# MBC5_1-4.net
KiCad netlist of a schematic drawn in EAGLE
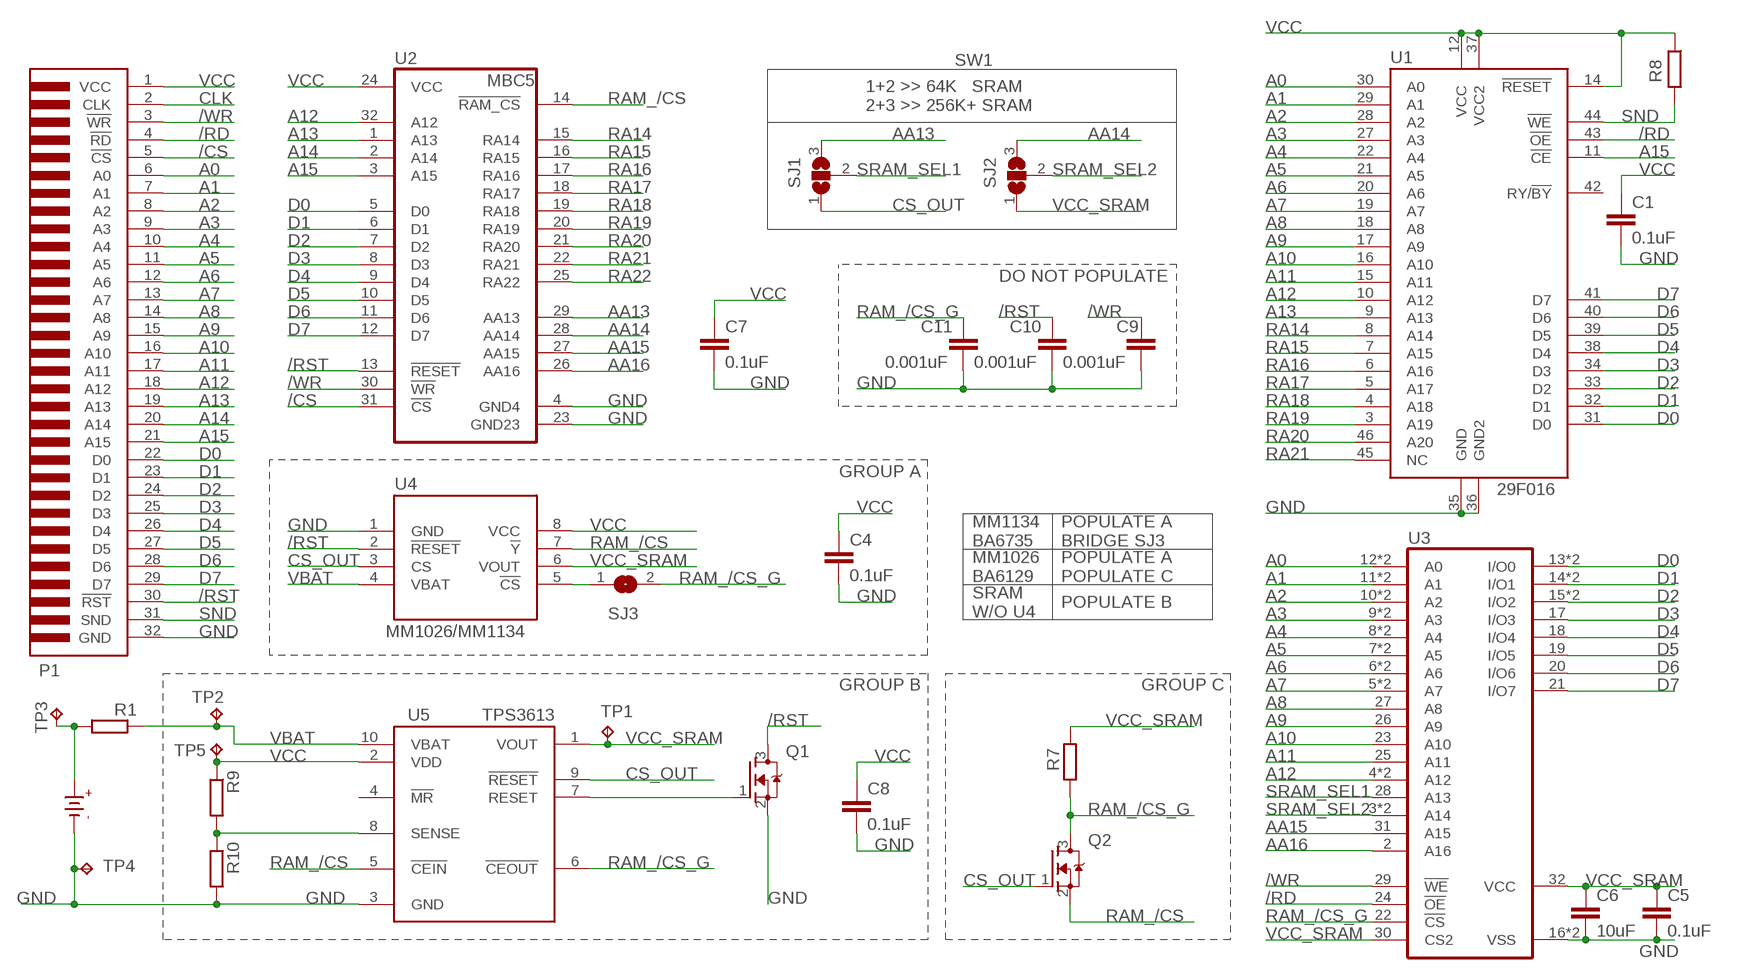
[diagram p0: schematic, sheet 1]

(export (version "E")
  (design (tool "Eeschema 10.0.6"))
  (components
    (comp (ref "B1")
      (value "CR2025")
      (footprint "eagle-import:CR2025")
      (libsource (lib "eagle-import") (part "CR2025"))
    )
    (comp (ref "C1")
      (value "0.1uF")
      (footprint "eagle-import:C0603")
      (libsource (lib "eagle-import") (part "C-EUC0603"))
    )
    (comp (ref "C4")
      (value "0.1uF")
      (footprint "eagle-import:C0603")
      (libsource (lib "eagle-import") (part "C-EUC0603"))
    )
    (comp (ref "C5")
      (value "0.1uF")
      (footprint "eagle-import:C0603")
      (libsource (lib "eagle-import") (part "C-EUC0603"))
    )
    (comp (ref "C6")
      (value "10uF")
      (footprint "eagle-import:C0603")
      (libsource (lib "eagle-import") (part "C-EUC0603"))
    )
    (comp (ref "C7")
      (value "0.1uF")
      (footprint "eagle-import:C0603")
      (libsource (lib "eagle-import") (part "C-EUC0603"))
    )
    (comp (ref "C8")
      (value "0.1uF")
      (footprint "eagle-import:C0603")
      (libsource (lib "eagle-import") (part "C-EUC0603"))
    )
    (comp (ref "C9")
      (value "0.001uF")
      (footprint "eagle-import:C0603")
      (libsource (lib "eagle-import") (part "C-EUC0603"))
    )
    (comp (ref "C10")
      (value "0.001uF")
      (footprint "eagle-import:C0603")
      (libsource (lib "eagle-import") (part "C-EUC0603"))
    )
    (comp (ref "C11")
      (value "0.001uF")
      (footprint "eagle-import:C0603")
      (libsource (lib "eagle-import") (part "C-EUC0603"))
    )
    (comp (ref "P1")
      (value "GBC_CARTTAB")
      (footprint "eagle-import:GBC_CART_TABBED")
      (libsource (lib "eagle-import") (part "GBC_CARTTAB"))
    )
    (comp (ref "Q1")
      (value "2N7002")
      (footprint "eagle-import:SOT23")
      (libsource (lib "eagle-import") (part "MOSFET-NREFLOW"))
    )
    (comp (ref "Q2")
      (value "2N7002")
      (footprint "eagle-import:SOT23")
      (libsource (lib "eagle-import") (part "MOSFET-NREFLOW"))
    )
    (comp (ref "R1")
      (value "RR0603")
      (footprint "eagle-import:R0603")
      (libsource (lib "eagle-import") (part "RR0603"))
    )
    (comp (ref "R7")
      (value "RR0603")
      (footprint "eagle-import:R0603")
      (libsource (lib "eagle-import") (part "RR0603"))
    )
    (comp (ref "R8")
      (value "RR0603")
      (footprint "eagle-import:R0603")
      (libsource (lib "eagle-import") (part "RR0603"))
    )
    (comp (ref "R9")
      (value "RR0603")
      (footprint "eagle-import:R0603")
      (libsource (lib "eagle-import") (part "RR0603"))
    )
    (comp (ref "R10")
      (value "RR0603")
      (footprint "eagle-import:R0603")
      (libsource (lib "eagle-import") (part "RR0603"))
    )
    (comp (ref "SJ1")
      (value "SJ2W")
      (footprint "eagle-import:SJ_2")
      (libsource (lib "eagle-import") (part "SJ2W"))
    )
    (comp (ref "SJ2")
      (value "SJ2W")
      (footprint "eagle-import:SJ_2")
      (libsource (lib "eagle-import") (part "SJ2W"))
    )
    (comp (ref "SJ3") (value "SJ") (footprint "eagle-import:SJ") (libsource (lib "eagle-import") (part "SJ")))
    (comp (ref "TP1")
      (value "TPB1,27")
      (footprint "eagle-import:B1,27")
      (libsource (lib "eagle-import") (part "TPB1,27"))
    )
    (comp (ref "TP2")
      (value "TPB1,27")
      (footprint "eagle-import:B1,27")
      (libsource (lib "eagle-import") (part "TPB1,27"))
    )
    (comp (ref "TP3")
      (value "TPB1,27")
      (footprint "eagle-import:B1,27")
      (libsource (lib "eagle-import") (part "TPB1,27"))
    )
    (comp (ref "TP4")
      (value "TPB1,27")
      (footprint "eagle-import:B1,27")
      (libsource (lib "eagle-import") (part "TPB1,27"))
    )
    (comp (ref "TP5")
      (value "TPB1,27")
      (footprint "eagle-import:B1,27")
      (libsource (lib "eagle-import") (part "TPB1,27"))
    )
    (comp (ref "U1")
      (value "29F016")
      (footprint "eagle-import:TSOP-48")
      (libsource (lib "eagle-import") (part "29F016"))
    )
    (comp (ref "U2")
      (value "MBC5")
      (footprint "eagle-import:QFP-32")
      (libsource (lib "eagle-import") (part "MBC5"))
    )
    (comp (ref "U3")
      (value "1008L")
      (footprint "eagle-import:SO32L_L")
      (libsource (lib "eagle-import") (part "1008L"))
    )
    (comp (ref "U4")
      (value "MM1134")
      (footprint "eagle-import:SOIC-8")
      (libsource (lib "eagle-import") (part "MM1134"))
    )
    (comp (ref "U5")
      (value "TPS3613")
      (footprint "eagle-import:MSOP-10")
      (libsource (lib "eagle-import") (part "TPS3613"))
    )
  )
  (nets
    (net (code "1") (name "/A0") (class "Default")
      (node (ref "P1") (pin "6") (pinfunction "A0_6") (pintype "output"))
      (node (ref "U1") (pin "30") (pinfunction "A0_30") (pintype "input"))
      (node (ref "U3") (pin "12") (pinfunction "A0_12") (pintype "input"))
      (node (ref "U3") (pin "L12") (pinfunction "A0_L12") (pintype "input"))
    )
    (net (code "2") (name "/A1") (class "Default")
      (node (ref "P1") (pin "7") (pinfunction "A1_7") (pintype "output"))
      (node (ref "U1") (pin "29") (pinfunction "A1_29") (pintype "input"))
      (node (ref "U3") (pin "11") (pinfunction "A1_11") (pintype "input"))
      (node (ref "U3") (pin "L11") (pinfunction "A1_L11") (pintype "input"))
    )
    (net (code "3") (name "/A2") (class "Default")
      (node (ref "P1") (pin "8") (pinfunction "A2_8") (pintype "output"))
      (node (ref "U1") (pin "28") (pinfunction "A2_28") (pintype "input"))
      (node (ref "U3") (pin "10") (pinfunction "A2_10") (pintype "input"))
      (node (ref "U3") (pin "L10") (pinfunction "A2_L10") (pintype "input"))
    )
    (net (code "4") (name "/A3") (class "Default")
      (node (ref "P1") (pin "9") (pinfunction "A3_9") (pintype "output"))
      (node (ref "U1") (pin "27") (pinfunction "A3_27") (pintype "input"))
      (node (ref "U3") (pin "9") (pinfunction "A3_9") (pintype "input"))
      (node (ref "U3") (pin "L9") (pinfunction "A3_L9") (pintype "input"))
    )
    (net (code "5") (name "/A4") (class "Default")
      (node (ref "P1") (pin "10") (pinfunction "A4_10") (pintype "output"))
      (node (ref "U1") (pin "22") (pinfunction "A4_22") (pintype "input"))
      (node (ref "U3") (pin "8") (pinfunction "A4_8") (pintype "input"))
      (node (ref "U3") (pin "L8") (pinfunction "A4_L8") (pintype "input"))
    )
    (net (code "6") (name "/A5") (class "Default")
      (node (ref "P1") (pin "11") (pinfunction "A5_11") (pintype "output"))
      (node (ref "U1") (pin "21") (pinfunction "A5_21") (pintype "input"))
      (node (ref "U3") (pin "7") (pinfunction "A5_7") (pintype "input"))
      (node (ref "U3") (pin "L7") (pinfunction "A5_L7") (pintype "input"))
    )
    (net (code "7") (name "/A6") (class "Default")
      (node (ref "P1") (pin "12") (pinfunction "A6_12") (pintype "output"))
      (node (ref "U1") (pin "20") (pinfunction "A6_20") (pintype "input"))
      (node (ref "U3") (pin "6") (pinfunction "A6_6") (pintype "input"))
      (node (ref "U3") (pin "L6") (pinfunction "A6_L6") (pintype "input"))
    )
    (net (code "8") (name "/A7") (class "Default")
      (node (ref "P1") (pin "13") (pinfunction "A7_13") (pintype "output"))
      (node (ref "U1") (pin "19") (pinfunction "A7_19") (pintype "input"))
      (node (ref "U3") (pin "5") (pinfunction "A7_5") (pintype "input"))
      (node (ref "U3") (pin "L5") (pinfunction "A7_L5") (pintype "input"))
    )
    (net (code "9") (name "/A8") (class "Default")
      (node (ref "P1") (pin "14") (pinfunction "A8_14") (pintype "output"))
      (node (ref "U1") (pin "18") (pinfunction "A8_18") (pintype "input"))
      (node (ref "U3") (pin "27") (pinfunction "A8_27") (pintype "input"))
    )
    (net (code "10") (name "/A9") (class "Default")
      (node (ref "P1") (pin "15") (pinfunction "A9_15") (pintype "output"))
      (node (ref "U1") (pin "17") (pinfunction "A9_17") (pintype "input"))
      (node (ref "U3") (pin "26") (pinfunction "A9_26") (pintype "input"))
    )
    (net (code "11") (name "/A10") (class "Default")
      (node (ref "P1") (pin "16") (pinfunction "A10_16") (pintype "output"))
      (node (ref "U1") (pin "16") (pinfunction "A10_16") (pintype "input"))
      (node (ref "U3") (pin "23") (pinfunction "A10_23") (pintype "input"))
    )
    (net (code "12") (name "/A11") (class "Default")
      (node (ref "P1") (pin "17") (pinfunction "A11_17") (pintype "output"))
      (node (ref "U1") (pin "15") (pinfunction "A11_15") (pintype "input"))
      (node (ref "U3") (pin "25") (pinfunction "A11_25") (pintype "input"))
    )
    (net (code "13") (name "/A12") (class "Default")
      (node (ref "P1") (pin "18") (pinfunction "A12_18") (pintype "output"))
      (node (ref "U1") (pin "10") (pinfunction "A12_10") (pintype "input"))
      (node (ref "U2") (pin "32") (pinfunction "A12_32") (pintype "input"))
      (node (ref "U3") (pin "4") (pinfunction "A12_4") (pintype "input"))
      (node (ref "U3") (pin "L4") (pinfunction "A12_L4") (pintype "input"))
    )
    (net (code "14") (name "/A13") (class "Default")
      (node (ref "P1") (pin "19") (pinfunction "A13_19") (pintype "output"))
      (node (ref "U1") (pin "9") (pinfunction "A13_9") (pintype "input"))
      (node (ref "U2") (pin "1") (pinfunction "A13_1") (pintype "input"))
    )
    (net (code "15") (name "/A14") (class "Default")
      (node (ref "P1") (pin "20") (pinfunction "A14_20") (pintype "output"))
      (node (ref "U2") (pin "2") (pinfunction "A14_2") (pintype "input"))
    )
    (net (code "16") (name "/A15") (class "Default")
      (node (ref "P1") (pin "21") (pinfunction "A15_21") (pintype "output"))
      (node (ref "U1") (pin "11") (pinfunction "~{CE}_11") (pintype "input"))
      (node (ref "U2") (pin "3") (pinfunction "A15_3") (pintype "input"))
    )
    (net (code "17") (name "/AA13") (class "Default")
      (node (ref "SJ1") (pin "3") (pinfunction "3_3") (pintype "passive"))
      (node (ref "U2") (pin "29") (pinfunction "AA13_29") (pintype "output"))
    )
    (net (code "18") (name "/AA14") (class "Default")
      (node (ref "SJ2") (pin "3") (pinfunction "3_3") (pintype "passive"))
      (node (ref "U2") (pin "28") (pinfunction "AA14_28") (pintype "output"))
    )
    (net (code "19") (name "/AA15") (class "Default")
      (node (ref "U2") (pin "27") (pinfunction "AA15_27") (pintype "output"))
      (node (ref "U3") (pin "31") (pinfunction "A15_31") (pintype "input"))
    )
    (net (code "20") (name "/AA16") (class "Default")
      (node (ref "U2") (pin "26") (pinfunction "AA16_26") (pintype "output"))
      (node (ref "U3") (pin "2") (pinfunction "A16_2") (pintype "input"))
    )
    (net (code "21") (name "/CLK") (class "Default")
      (node (ref "P1") (pin "2") (pinfunction "CLK_2") (pintype "output"))
    )
    (net (code "22") (name "/CS_OUT") (class "Default")
      (node (ref "Q2") (pin "1") (pinfunction "G_1") (pintype "bidirectional"))
      (node (ref "SJ1") (pin "1") (pinfunction "1_1") (pintype "passive"))
      (node (ref "U4") (pin "3") (pinfunction "CS_3") (pintype "output"))
      (node (ref "U5") (pin "9") (pinfunction "~{RESET}_9") (pintype "output"))
    )
    (net (code "23") (name "/D0") (class "Default")
      (node (ref "P1") (pin "22") (pinfunction "D0_22") (pintype "bidirectional"))
      (node (ref "U1") (pin "31") (pinfunction "D0_31") (pintype "bidirectional"))
      (node (ref "U2") (pin "5") (pinfunction "D0_5") (pintype "input"))
      (node (ref "U3") (pin "13") (pinfunction "I/O0_13") (pintype "bidirectional"))
      (node (ref "U3") (pin "L13") (pinfunction "I/O0_L13") (pintype "bidirectional"))
    )
    (net (code "24") (name "/D1") (class "Default")
      (node (ref "P1") (pin "23") (pinfunction "D1_23") (pintype "bidirectional"))
      (node (ref "U1") (pin "32") (pinfunction "D1_32") (pintype "bidirectional"))
      (node (ref "U2") (pin "6") (pinfunction "D1_6") (pintype "input"))
      (node (ref "U3") (pin "14") (pinfunction "I/O1_14") (pintype "bidirectional"))
      (node (ref "U3") (pin "L14") (pinfunction "I/O1_L14") (pintype "bidirectional"))
    )
    (net (code "25") (name "/D2") (class "Default")
      (node (ref "P1") (pin "24") (pinfunction "D2_24") (pintype "bidirectional"))
      (node (ref "U1") (pin "33") (pinfunction "D2_33") (pintype "bidirectional"))
      (node (ref "U2") (pin "7") (pinfunction "D2_7") (pintype "input"))
      (node (ref "U3") (pin "15") (pinfunction "I/O2_15") (pintype "bidirectional"))
      (node (ref "U3") (pin "L15") (pinfunction "I/O2_L15") (pintype "bidirectional"))
    )
    (net (code "26") (name "/D3") (class "Default")
      (node (ref "P1") (pin "25") (pinfunction "D3_25") (pintype "bidirectional"))
      (node (ref "U1") (pin "34") (pinfunction "D3_34") (pintype "bidirectional"))
      (node (ref "U2") (pin "8") (pinfunction "D3_8") (pintype "input"))
      (node (ref "U3") (pin "17") (pinfunction "I/O3_17") (pintype "bidirectional"))
    )
    (net (code "27") (name "/D4") (class "Default")
      (node (ref "P1") (pin "26") (pinfunction "D4_26") (pintype "bidirectional"))
      (node (ref "U1") (pin "38") (pinfunction "D4_38") (pintype "bidirectional"))
      (node (ref "U2") (pin "9") (pinfunction "D4_9") (pintype "input"))
      (node (ref "U3") (pin "18") (pinfunction "I/O4_18") (pintype "bidirectional"))
    )
    (net (code "28") (name "/D5") (class "Default")
      (node (ref "P1") (pin "27") (pinfunction "D5_27") (pintype "bidirectional"))
      (node (ref "U1") (pin "39") (pinfunction "D5_39") (pintype "bidirectional"))
      (node (ref "U2") (pin "10") (pinfunction "D5_10") (pintype "input"))
      (node (ref "U3") (pin "19") (pinfunction "I/O5_19") (pintype "bidirectional"))
    )
    (net (code "29") (name "/D6") (class "Default")
      (node (ref "P1") (pin "28") (pinfunction "D6_28") (pintype "bidirectional"))
      (node (ref "U1") (pin "40") (pinfunction "D6_40") (pintype "bidirectional"))
      (node (ref "U2") (pin "11") (pinfunction "D6_11") (pintype "input"))
      (node (ref "U3") (pin "20") (pinfunction "I/O6_20") (pintype "bidirectional"))
    )
    (net (code "30") (name "/D7") (class "Default")
      (node (ref "P1") (pin "29") (pinfunction "D7_29") (pintype "bidirectional"))
      (node (ref "U1") (pin "41") (pinfunction "D7_41") (pintype "bidirectional"))
      (node (ref "U2") (pin "12") (pinfunction "D7_12") (pintype "input"))
      (node (ref "U3") (pin "21") (pinfunction "I/O7_21") (pintype "bidirectional"))
    )
    (net (code "31") (name "/GND") (class "Default")
      (node (ref "B1") (pin "-") (pinfunction "-_-") (pintype "power_in"))
      (node (ref "C1") (pin "2") (pinfunction "2_2") (pintype "passive"))
      (node (ref "C10") (pin "2") (pinfunction "2_2") (pintype "passive"))
      (node (ref "C11") (pin "2") (pinfunction "2_2") (pintype "passive"))
      (node (ref "C4") (pin "2") (pinfunction "2_2") (pintype "passive"))
      (node (ref "C5") (pin "2") (pinfunction "2_2") (pintype "passive"))
      (node (ref "C6") (pin "2") (pinfunction "2_2") (pintype "passive"))
      (node (ref "C7") (pin "2") (pinfunction "2_2") (pintype "passive"))
      (node (ref "C8") (pin "2") (pinfunction "2_2") (pintype "passive"))
      (node (ref "C9") (pin "2") (pinfunction "2_2") (pintype "passive"))
      (node (ref "P1") (pin "32") (pinfunction "GND_32") (pintype "power_in"))
      (node (ref "Q1") (pin "2") (pinfunction "S_2") (pintype "bidirectional"))
      (node (ref "R10") (pin "2") (pinfunction "2_2") (pintype "passive"))
      (node (ref "TP4") (pin "TP") (pinfunction "TP_TP") (pintype "input"))
      (node (ref "U1") (pin "35") (pinfunction "GND_35") (pintype "power_in"))
      (node (ref "U1") (pin "36") (pinfunction "GND2_36") (pintype "power_in"))
      (node (ref "U2") (pin "23") (pinfunction "GND23_23") (pintype "power_in"))
      (node (ref "U2") (pin "4") (pinfunction "GND4_4") (pintype "power_in"))
      (node (ref "U3") (pin "16") (pinfunction "VSS_16") (pintype "power_in"))
      (node (ref "U3") (pin "L16") (pinfunction "VSS_L16") (pintype "power_in"))
      (node (ref "U4") (pin "1") (pinfunction "GND_1") (pintype "power_in"))
      (node (ref "U5") (pin "3") (pinfunction "GND_3") (pintype "power_in"))
    )
    (net (code "32") (name "/RA14") (class "Default")
      (node (ref "U1") (pin "8") (pinfunction "A14_8") (pintype "input"))
      (node (ref "U2") (pin "15") (pinfunction "RA14_15") (pintype "output"))
    )
    (net (code "33") (name "/RA15") (class "Default")
      (node (ref "U1") (pin "7") (pinfunction "A15_7") (pintype "input"))
      (node (ref "U2") (pin "16") (pinfunction "RA15_16") (pintype "output"))
    )
    (net (code "34") (name "/RA16") (class "Default")
      (node (ref "U1") (pin "6") (pinfunction "A16_6") (pintype "input"))
      (node (ref "U2") (pin "17") (pinfunction "RA16_17") (pintype "output"))
    )
    (net (code "35") (name "/RA17") (class "Default")
      (node (ref "U1") (pin "5") (pinfunction "A17_5") (pintype "input"))
      (node (ref "U2") (pin "18") (pinfunction "RA17_18") (pintype "output"))
    )
    (net (code "36") (name "/RA18") (class "Default")
      (node (ref "U1") (pin "4") (pinfunction "A18_4") (pintype "input"))
      (node (ref "U2") (pin "19") (pinfunction "RA18_19") (pintype "output"))
    )
    (net (code "37") (name "/RA19") (class "Default")
      (node (ref "U1") (pin "3") (pinfunction "A19_3") (pintype "input"))
      (node (ref "U2") (pin "20") (pinfunction "RA19_20") (pintype "output"))
    )
    (net (code "38") (name "/RA20") (class "Default")
      (node (ref "U1") (pin "46") (pinfunction "A20_46") (pintype "input"))
      (node (ref "U2") (pin "21") (pinfunction "RA20_21") (pintype "output"))
    )
    (net (code "39") (name "/RA21") (class "Default")
      (node (ref "U1") (pin "45") (pinfunction "NC_45") (pintype "input"))
      (node (ref "U2") (pin "22") (pinfunction "RA21_22") (pintype "output"))
    )
    (net (code "40") (name "/RA22") (class "Default")
      (node (ref "U2") (pin "25") (pinfunction "RA22_25") (pintype "output"))
    )
    (net (code "41") (name "/RAM_{slash}CS") (class "Default")
      (node (ref "Q2") (pin "2") (pinfunction "S_2") (pintype "bidirectional"))
      (node (ref "U2") (pin "14") (pinfunction "~{RAM_CS}_14") (pintype "output"))
      (node (ref "U4") (pin "7") (pinfunction "~{Y}_7") (pintype "input"))
      (node (ref "U5") (pin "5") (pinfunction "~{CEIN}_5") (pintype "input"))
    )
    (net (code "42") (name "/RAM_{slash}CS_G") (class "Default")
      (node (ref "C11") (pin "1") (pinfunction "1_1") (pintype "passive"))
      (node (ref "Q2") (pin "3") (pinfunction "D_3") (pintype "bidirectional"))
      (node (ref "R7") (pin "1") (pinfunction "1_1") (pintype "passive"))
      (node (ref "SJ3") (pin "2") (pinfunction "2_2") (pintype "passive"))
      (node (ref "U3") (pin "22") (pinfunction "~{CS}_22") (pintype "input"))
      (node (ref "U5") (pin "6") (pinfunction "~{CEOUT}_6") (pintype "output"))
    )
    (net (code "43") (name "/SND") (class "Default")
      (node (ref "P1") (pin "31") (pinfunction "SND_31") (pintype "bidirectional"))
      (node (ref "R8") (pin "2") (pinfunction "2_2") (pintype "passive"))
      (node (ref "U1") (pin "44") (pinfunction "~{WE}_44") (pintype "input"))
    )
    (net (code "44") (name "/SRAM_SEL1") (class "Default")
      (node (ref "SJ1") (pin "2") (pinfunction "2_2") (pintype "passive"))
      (node (ref "U3") (pin "28") (pinfunction "A13_28") (pintype "input"))
    )
    (net (code "45") (name "/SRAM_SEL2") (class "Default")
      (node (ref "SJ2") (pin "2") (pinfunction "2_2") (pintype "passive"))
      (node (ref "U3") (pin "3") (pinfunction "A14_3") (pintype "input"))
      (node (ref "U3") (pin "L3") (pinfunction "A14_L3") (pintype "input"))
    )
    (net (code "46") (name "/VBAT") (class "Default")
      (node (ref "R1") (pin "1") (pinfunction "1_1") (pintype "passive"))
      (node (ref "TP2") (pin "TP") (pinfunction "TP_TP") (pintype "input"))
      (node (ref "U4") (pin "4") (pinfunction "VBAT_4") (pintype "power_in"))
      (node (ref "U5") (pin "10") (pinfunction "VBAT_10") (pintype "power_in"))
    )
    (net (code "47") (name "/VCC") (class "Default")
      (node (ref "C1") (pin "1") (pinfunction "1_1") (pintype "passive"))
      (node (ref "C4") (pin "1") (pinfunction "1_1") (pintype "passive"))
      (node (ref "C7") (pin "1") (pinfunction "1_1") (pintype "passive"))
      (node (ref "C8") (pin "1") (pinfunction "1_1") (pintype "passive"))
      (node (ref "P1") (pin "1") (pinfunction "VCC_1") (pintype "power_in"))
      (node (ref "R8") (pin "1") (pinfunction "1_1") (pintype "passive"))
      (node (ref "R9") (pin "1") (pinfunction "1_1") (pintype "passive"))
      (node (ref "TP5") (pin "TP") (pinfunction "TP_TP") (pintype "input"))
      (node (ref "U1") (pin "12") (pinfunction "VCC_12") (pintype "power_in"))
      (node (ref "U1") (pin "14") (pinfunction "~{RESET}_14") (pintype "input"))
      (node (ref "U1") (pin "37") (pinfunction "VCC2_37") (pintype "power_in"))
      (node (ref "U2") (pin "24") (pinfunction "VCC_24") (pintype "power_in"))
      (node (ref "U4") (pin "8") (pinfunction "VCC_8") (pintype "power_in"))
      (node (ref "U5") (pin "2") (pinfunction "VDD_2") (pintype "power_in"))
    )
    (net (code "48") (name "/VCC_SRAM") (class "Default")
      (node (ref "C5") (pin "1") (pinfunction "1_1") (pintype "passive"))
      (node (ref "C6") (pin "1") (pinfunction "1_1") (pintype "passive"))
      (node (ref "R7") (pin "2") (pinfunction "2_2") (pintype "passive"))
      (node (ref "SJ2") (pin "1") (pinfunction "1_1") (pintype "passive"))
      (node (ref "TP1") (pin "TP") (pinfunction "TP_TP") (pintype "input"))
      (node (ref "U3") (pin "30") (pinfunction "CS2_30") (pintype "input"))
      (node (ref "U3") (pin "32") (pinfunction "VCC_32") (pintype "power_in"))
      (node (ref "U4") (pin "6") (pinfunction "VOUT_6") (pintype "power_in"))
      (node (ref "U5") (pin "1") (pinfunction "VOUT_1") (pintype "power_in"))
    )
    (net (code "49") (name "/{slash}CS") (class "Default")
      (node (ref "P1") (pin "5") (pinfunction "~{CS}_5") (pintype "output"))
      (node (ref "U2") (pin "31") (pinfunction "~{CS}_31") (pintype "input"))
    )
    (net (code "50") (name "/{slash}RD") (class "Default")
      (node (ref "P1") (pin "4") (pinfunction "~{RD}_4") (pintype "output"))
      (node (ref "U1") (pin "43") (pinfunction "~{OE}_43") (pintype "input"))
      (node (ref "U3") (pin "24") (pinfunction "~{OE}_24") (pintype "input"))
    )
    (net (code "51") (name "/{slash}RST") (class "Default")
      (node (ref "C10") (pin "1") (pinfunction "1_1") (pintype "passive"))
      (node (ref "P1") (pin "30") (pinfunction "~{RST}_30") (pintype "bidirectional"))
      (node (ref "Q1") (pin "3") (pinfunction "D_3") (pintype "bidirectional"))
      (node (ref "U2") (pin "13") (pinfunction "~{RESET}_13") (pintype "input"))
      (node (ref "U4") (pin "2") (pinfunction "~{RESET}_2") (pintype "input"))
    )
    (net (code "52") (name "/{slash}WR") (class "Default")
      (node (ref "C9") (pin "1") (pinfunction "1_1") (pintype "passive"))
      (node (ref "P1") (pin "3") (pinfunction "~{WR}_3") (pintype "output"))
      (node (ref "U2") (pin "30") (pinfunction "~{WR}_30") (pintype "input"))
      (node (ref "U3") (pin "29") (pinfunction "~{WE}_29") (pintype "input"))
    )
    (net (code "53") (name "Net-(B1-Pad+)") (class "Default")
      (node (ref "B1") (pin "+") (pinfunction "+_+") (pintype "power_in"))
      (node (ref "R1") (pin "2") (pinfunction "2_2") (pintype "passive"))
      (node (ref "TP3") (pin "TP") (pinfunction "TP_TP") (pintype "input"))
    )
    (net (code "54") (name "Net-(Q1-G)") (class "Default")
      (node (ref "Q1") (pin "1") (pinfunction "G_1") (pintype "bidirectional"))
      (node (ref "U5") (pin "7") (pinfunction "RESET_7") (pintype "output"))
    )
    (net (code "55") (name "Net-(U4-~{CS})") (class "Default")
      (node (ref "SJ3") (pin "1") (pinfunction "1_1") (pintype "passive"))
      (node (ref "U4") (pin "5") (pinfunction "~{CS}_5") (pintype "output"))
    )
    (net (code "56") (name "Net-(U5-SENSE)") (class "Default")
      (node (ref "R10") (pin "1") (pinfunction "1_1") (pintype "passive"))
      (node (ref "R9") (pin "2") (pinfunction "2_2") (pintype "passive"))
      (node (ref "U5") (pin "8") (pinfunction "SENSE_8") (pintype "input"))
    )
    (net (code "57") (name "unconnected-(U1-RY{slash}~{BY}-Pad42)") (class "Default")
      (node (ref "U1") (pin "42") (pinfunction "RY/~{BY}_42") (pintype "output"))
    )
    (net (code "58") (name "unconnected-(U5-~{MR}-Pad4)") (class "Default")
      (node (ref "U5") (pin "4") (pinfunction "~{MR}_4") (pintype "input"))
    )
  )
)
